# MICHA.net
KiCad netlist of a schematic drawn in EAGLE
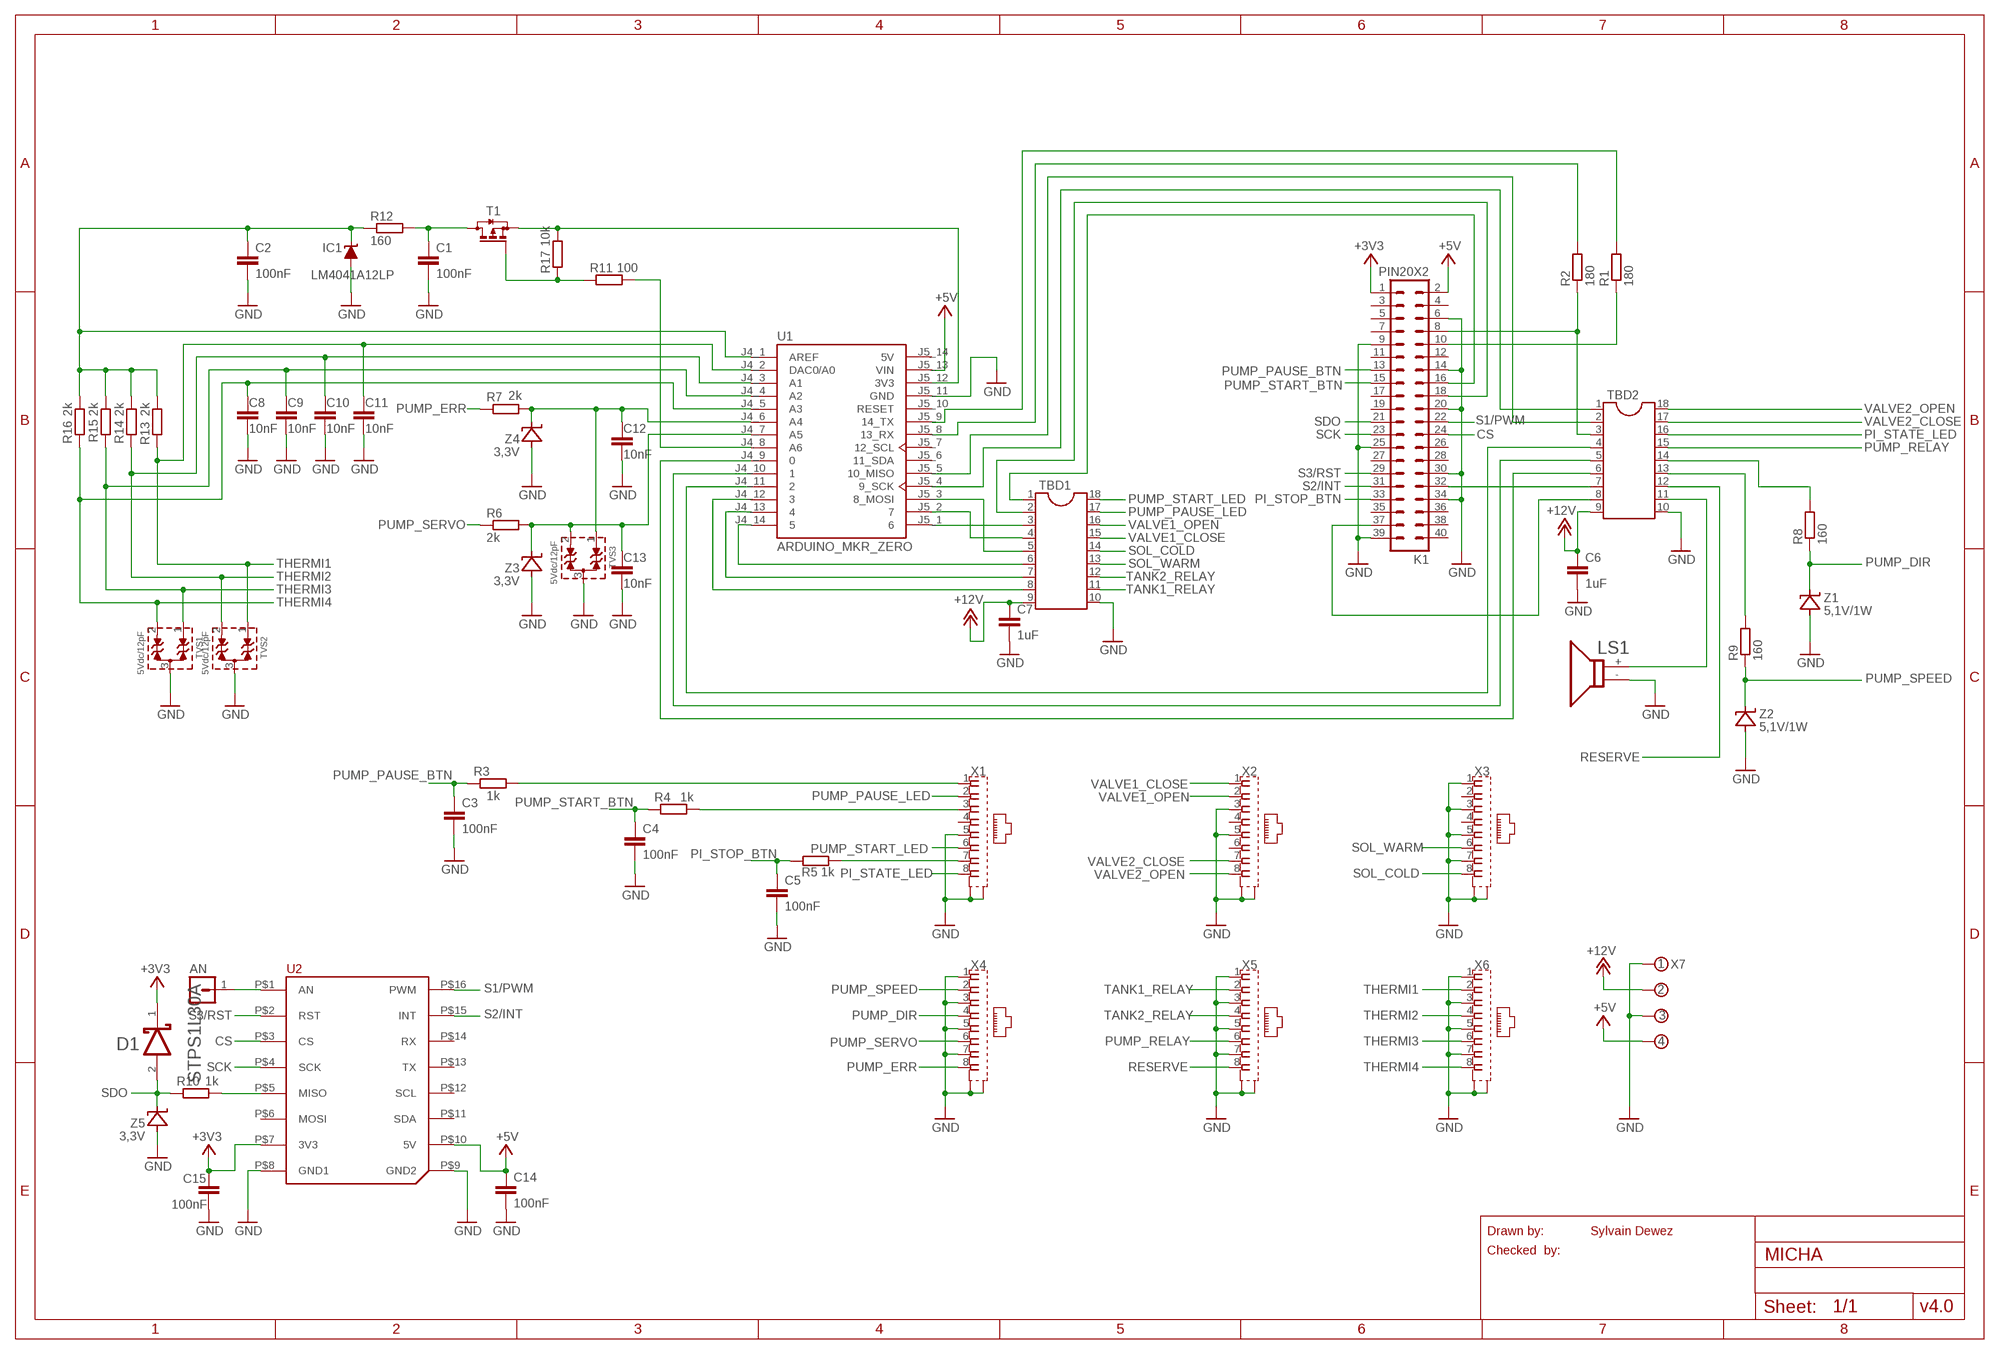
[diagram p0: schematic, sheet 1]

(export (version "E")
  (design (tool "Eeschema 10.0.6"))
  (components
    (comp (ref "AN")
      (value "MA01_PINHEADER")
      (footprint "eagle-import:MA01")
      (libsource (lib "eagle-import") (part "MA01_PINHEADER"))
    )
    (comp (ref "C1")
      (value "100nF")
      (footprint "eagle-import:C1206")
      (libsource (lib "eagle-import") (part "C-EUC1206"))
    )
    (comp (ref "C2")
      (value "100nF")
      (footprint "eagle-import:C1206")
      (libsource (lib "eagle-import") (part "C-EUC1206"))
    )
    (comp (ref "C3")
      (value "100nF")
      (footprint "eagle-import:C1206")
      (libsource (lib "eagle-import") (part "C-EUC1206"))
    )
    (comp (ref "C4")
      (value "100nF")
      (footprint "eagle-import:C1206")
      (libsource (lib "eagle-import") (part "C-EUC1206"))
    )
    (comp (ref "C5")
      (value "100nF")
      (footprint "eagle-import:C1206")
      (libsource (lib "eagle-import") (part "C-EUC1206"))
    )
    (comp (ref "C6")
      (value "1uF")
      (footprint "eagle-import:C1206")
      (libsource (lib "eagle-import") (part "C-EUC1206"))
    )
    (comp (ref "C7")
      (value "1uF")
      (footprint "eagle-import:C1206")
      (libsource (lib "eagle-import") (part "C-EUC1206"))
    )
    (comp (ref "C8")
      (value "10nF")
      (footprint "eagle-import:C1206")
      (libsource (lib "eagle-import") (part "C-EUC1206"))
    )
    (comp (ref "C9")
      (value "10nF")
      (footprint "eagle-import:C1206")
      (libsource (lib "eagle-import") (part "C-EUC1206"))
    )
    (comp (ref "C10")
      (value "10nF")
      (footprint "eagle-import:C1206")
      (libsource (lib "eagle-import") (part "C-EUC1206"))
    )
    (comp (ref "C11")
      (value "10nF")
      (footprint "eagle-import:C1206")
      (libsource (lib "eagle-import") (part "C-EUC1206"))
    )
    (comp (ref "C12")
      (value "10nF")
      (footprint "eagle-import:C1206")
      (libsource (lib "eagle-import") (part "C-EUC1206"))
    )
    (comp (ref "C13")
      (value "10nF")
      (footprint "eagle-import:C1206")
      (libsource (lib "eagle-import") (part "C-EUC1206"))
    )
    (comp (ref "C14")
      (value "100nF")
      (footprint "eagle-import:C1206")
      (libsource (lib "eagle-import") (part "C-EUC1206"))
    )
    (comp (ref "C15")
      (value "100nF")
      (footprint "eagle-import:C1206")
      (libsource (lib "eagle-import") (part "C-EUC1206"))
    )
    (comp (ref "D1")
      (value "STMICROELECTRONICS_STPS1L30ASTMICROELECTRONICS_STPS1L30A_0_0")
      (footprint "eagle-import:STMICROELECTRONICS_STPS1L30A_0")
      (fields
        (field (name "DIGIKEY_PART_NUMBER") "497-6577-1-ND")
        (field (name "MF") "STMicroelectronics")
        (field (name "MOUSER_PART_NUMBER") "511-STPS1L30A")
      )
      (libsource (lib "eagle-import") (part "STMICROELECTRONICS_STPS1L30ASTMICROELECTRONICS_STPS1L30A_0_0"))
    )
    (comp (ref "IC1")
      (value "LM4041A12LP")
      (footprint "eagle-import:LP_O-PBCY-W3")
      (libsource (lib "eagle-import") (part "LM4041LPA12"))
    )
    (comp (ref "K1")
      (value "PIN20X2")
      (footprint "eagle-import:PIN_20X2")
      (libsource (lib "eagle-import") (part "PIN20X2"))
    )
    (comp (ref "LS1")
      (value "RSPRO-BUZZER-7800743")
      (footprint "eagle-import:RSPRO-BUZZER-7800743")
      (libsource (lib "eagle-import") (part "RSPRO-BUZZER-7800743"))
    )
    (comp (ref "R1")
      (value "180")
      (footprint "eagle-import:R1206")
      (libsource (lib "eagle-import") (part "resistor_R-EU_R1206"))
    )
    (comp (ref "R2")
      (value "180")
      (footprint "eagle-import:R1206")
      (libsource (lib "eagle-import") (part "resistor_R-EU_R1206"))
    )
    (comp (ref "R3")
      (value "1k")
      (footprint "eagle-import:R1206")
      (libsource (lib "eagle-import") (part "resistor_R-EU_R1206"))
    )
    (comp (ref "R4")
      (value "1k")
      (footprint "eagle-import:R1206")
      (libsource (lib "eagle-import") (part "resistor_R-EU_R1206"))
    )
    (comp (ref "R5")
      (value "1k")
      (footprint "eagle-import:R1206")
      (libsource (lib "eagle-import") (part "resistor_R-EU_R1206"))
    )
    (comp (ref "R6")
      (value "2k")
      (footprint "eagle-import:R1206")
      (libsource (lib "eagle-import") (part "resistor_R-EU_R1206"))
    )
    (comp (ref "R7")
      (value "2k")
      (footprint "eagle-import:R1206")
      (libsource (lib "eagle-import") (part "resistor_R-EU_R1206"))
    )
    (comp (ref "R8")
      (value "160")
      (footprint "eagle-import:R1210")
      (libsource (lib "eagle-import") (part "R-EU_R1210"))
    )
    (comp (ref "R9")
      (value "160")
      (footprint "eagle-import:R1210")
      (libsource (lib "eagle-import") (part "R-EU_R1210"))
    )
    (comp (ref "R10")
      (value "1k")
      (footprint "eagle-import:R1206")
      (libsource (lib "eagle-import") (part "resistor_R-EU_R1206"))
    )
    (comp (ref "R11")
      (value "100")
      (footprint "eagle-import:R1206")
      (libsource (lib "eagle-import") (part "resistor_R-EU_R1206"))
    )
    (comp (ref "R12")
      (value "160")
      (footprint "eagle-import:R1210")
      (libsource (lib "eagle-import") (part "R-EU_R1210"))
    )
    (comp (ref "R13")
      (value "2k")
      (footprint "eagle-import:R1206")
      (libsource (lib "eagle-import") (part "resistor_R-EU_R1206"))
    )
    (comp (ref "R14")
      (value "2k")
      (footprint "eagle-import:R1206")
      (libsource (lib "eagle-import") (part "resistor_R-EU_R1206"))
    )
    (comp (ref "R15")
      (value "2k")
      (footprint "eagle-import:R1206")
      (libsource (lib "eagle-import") (part "resistor_R-EU_R1206"))
    )
    (comp (ref "R16")
      (value "2k")
      (footprint "eagle-import:R1206")
      (libsource (lib "eagle-import") (part "resistor_R-EU_R1206"))
    )
    (comp (ref "R17")
      (value "10k")
      (footprint "eagle-import:R1206")
      (libsource (lib "eagle-import") (part "resistor_R-EU_R1206"))
    )
    (comp (ref "T1")
      (value "BSS84")
      (footprint "eagle-import:SOT23")
      (libsource (lib "eagle-import") (part "BSS84"))
    )
    (comp (ref "TBD1")
      (value "DIL18S")
      (footprint "eagle-import:SOCKET-18")
      (libsource (lib "eagle-import") (part "DIL18S"))
    )
    (comp (ref "TBD2")
      (value "DIL18S")
      (footprint "eagle-import:SOCKET-18")
      (libsource (lib "eagle-import") (part "DIL18S"))
    )
    (comp (ref "TVS1")
      (value "5Vdc/12pF")
      (footprint "eagle-import:WE-TVS_SOT23-3L")
      (libsource (lib "eagle-import") (part "WE-TVS_SOT23-3L_824022"))
    )
    (comp (ref "TVS2")
      (value "5Vdc/12pF")
      (footprint "eagle-import:WE-TVS_SOT23-3L")
      (libsource (lib "eagle-import") (part "WE-TVS_SOT23-3L_824022"))
    )
    (comp (ref "TVS3")
      (value "5Vdc/12pF")
      (footprint "eagle-import:WE-TVS_SOT23-3L")
      (libsource (lib "eagle-import") (part "WE-TVS_SOT23-3L_824022"))
    )
    (comp (ref "U1")
      (value "ARDUINO_MKR_ZERO")
      (footprint "eagle-import:MODULE_ARDUINO_MKR_ZERO")
      (fields (field (name "MF") "Arduino") (field (name "MP") "ARDUINO MKR ZERO"))
      (libsource (lib "eagle-import") (part "ARDUINO_MKR_ZERO"))
    )
    (comp (ref "U2")
      (value "MIKROE_CLICK")
      (footprint "eagle-import:MIKROE_BUS_MIDI_NOLABEL")
      (libsource (lib "eagle-import") (part "MIKROE_CLICK"))
    )
    (comp (ref "X1")
      (value "RJ45-RJULE4318101")
      (footprint "eagle-import:RJ45-RJULE4318101")
      (libsource (lib "eagle-import") (part "RJ45-RJULE4318101"))
    )
    (comp (ref "X2")
      (value "RJ45-RJULE4318101")
      (footprint "eagle-import:RJ45-RJULE4318101")
      (libsource (lib "eagle-import") (part "RJ45-RJULE4318101"))
    )
    (comp (ref "X3")
      (value "RJ45-RJULE4318101")
      (footprint "eagle-import:RJ45-RJULE4318101")
      (libsource (lib "eagle-import") (part "RJ45-RJULE4318101"))
    )
    (comp (ref "X4")
      (value "RJ45-RJULE4318101")
      (footprint "eagle-import:RJ45-RJULE4318101")
      (libsource (lib "eagle-import") (part "RJ45-RJULE4318101"))
    )
    (comp (ref "X5")
      (value "RJ45-RJULE4318101")
      (footprint "eagle-import:RJ45-RJULE4318101")
      (libsource (lib "eagle-import") (part "RJ45-RJULE4318101"))
    )
    (comp (ref "X6")
      (value "RJ45-RJULE4318101")
      (footprint "eagle-import:RJ45-RJULE4318101")
      (libsource (lib "eagle-import") (part "RJ45-RJULE4318101"))
    )
    (comp (ref "X7")
      (value "BUCHANAN_4_3.5MM")
      (footprint "eagle-import:BUCHANAN_4_3.5MM")
      (libsource (lib "eagle-import") (part "BUCHANAN_4_3.5MM"))
    )
    (comp (ref "Z1")
      (value "5,1V/1W")
      (footprint "eagle-import:ZENER_SMA")
      (libsource (lib "eagle-import") (part "ZENER_SMA"))
    )
    (comp (ref "Z2")
      (value "5,1V/1W")
      (footprint "eagle-import:ZENER_SMA")
      (libsource (lib "eagle-import") (part "ZENER_SMA"))
    )
    (comp (ref "Z3")
      (value "3,3V")
      (footprint "eagle-import:ZENER_SMA")
      (libsource (lib "eagle-import") (part "ZENER_SMA"))
    )
    (comp (ref "Z4")
      (value "3,3V")
      (footprint "eagle-import:ZENER_SMA")
      (libsource (lib "eagle-import") (part "ZENER_SMA"))
    )
    (comp (ref "Z5")
      (value "3,3V")
      (footprint "eagle-import:ZENER_SMA")
      (libsource (lib "eagle-import") (part "ZENER_SMA"))
    )
  )
  (nets
    (net (code "1") (name "+3V3") (class "Default")
      (node (ref "C15") (pin "1") (pinfunction "1_1") (pintype "passive"))
      (node (ref "D1") (pin "1") (pinfunction "CATHODE_1") (pintype "bidirectional"))
      (node (ref "K1") (pin "1") (pinfunction "1_1") (pintype "passive"))
      (node (ref "U2") (pin "P$7") (pinfunction "3V3_P$7") (pintype "bidirectional"))
    )
    (net (code "2") (name "+5V") (class "Default")
      (node (ref "C14") (pin "1") (pinfunction "1_1") (pintype "passive"))
      (node (ref "K1") (pin "2") (pinfunction "2_2") (pintype "passive"))
      (node (ref "U1") (pin "J5_13") (pinfunction "VIN_J5_13") (pintype "power_in"))
      (node (ref "U2") (pin "P$10") (pinfunction "5V_P$10") (pintype "bidirectional"))
      (node (ref "X7") (pin "4") (pinfunction "KL3_4") (pintype "passive"))
    )
    (net (code "3") (name "+12V") (class "Default")
      (node (ref "C6") (pin "1") (pinfunction "1_1") (pintype "passive"))
      (node (ref "C7") (pin "1") (pinfunction "1_1") (pintype "passive"))
      (node (ref "TBD1") (pin "9") (pinfunction "9_9") (pintype "passive"))
      (node (ref "TBD2") (pin "9") (pinfunction "9_9") (pintype "passive"))
      (node (ref "X7") (pin "2") (pinfunction "KL1_2") (pintype "passive"))
    )
    (net (code "4") (name "/5V") (class "Default")
      (node (ref "U1") (pin "J5_14") (pinfunction "5V_J5_14") (pintype "power_in"))
    )
    (net (code "5") (name "/CS") (class "Default")
      (node (ref "K1") (pin "24") (pinfunction "24_24") (pintype "passive"))
      (node (ref "U2") (pin "P$3") (pinfunction "CS_P$3") (pintype "bidirectional"))
    )
    (net (code "6") (name "/PI_STATE_LED") (class "Default")
      (node (ref "TBD2") (pin "16") (pinfunction "16_16") (pintype "passive"))
      (node (ref "X1") (pin "8") (pinfunction "8_8") (pintype "passive"))
    )
    (net (code "7") (name "/PI_STOP_BTN") (class "Default")
      (node (ref "C5") (pin "1") (pinfunction "1_1") (pintype "passive"))
      (node (ref "K1") (pin "33") (pinfunction "33_33") (pintype "passive"))
      (node (ref "R5") (pin "1") (pinfunction "1_1") (pintype "passive"))
    )
    (net (code "8") (name "/PUMP_DIR") (class "Default")
      (node (ref "R8") (pin "1") (pinfunction "1_1") (pintype "passive"))
      (node (ref "X4") (pin "4") (pinfunction "4_4") (pintype "passive"))
      (node (ref "Z1") (pin "C") (pinfunction "C_C") (pintype "passive"))
    )
    (net (code "9") (name "/PUMP_ERR") (class "Default")
      (node (ref "R7") (pin "1") (pinfunction "1_1") (pintype "passive"))
      (node (ref "X4") (pin "8") (pinfunction "8_8") (pintype "passive"))
    )
    (net (code "10") (name "/PUMP_PAUSE_BTN") (class "Default")
      (node (ref "C3") (pin "1") (pinfunction "1_1") (pintype "passive"))
      (node (ref "K1") (pin "13") (pinfunction "13_13") (pintype "passive"))
      (node (ref "R3") (pin "1") (pinfunction "1_1") (pintype "passive"))
    )
    (net (code "11") (name "/PUMP_PAUSE_LED") (class "Default")
      (node (ref "TBD1") (pin "17") (pinfunction "17_17") (pintype "passive"))
      (node (ref "X1") (pin "2") (pinfunction "2_2") (pintype "passive"))
    )
    (net (code "12") (name "/PUMP_RELAY") (class "Default")
      (node (ref "TBD2") (pin "15") (pinfunction "15_15") (pintype "passive"))
      (node (ref "X5") (pin "6") (pinfunction "6_6") (pintype "passive"))
    )
    (net (code "13") (name "/PUMP_SERVO") (class "Default")
      (node (ref "R6") (pin "1") (pinfunction "1_1") (pintype "passive"))
      (node (ref "X4") (pin "6") (pinfunction "6_6") (pintype "passive"))
    )
    (net (code "14") (name "/PUMP_SPEED") (class "Default")
      (node (ref "R9") (pin "1") (pinfunction "1_1") (pintype "passive"))
      (node (ref "X4") (pin "2") (pinfunction "2_2") (pintype "passive"))
      (node (ref "Z2") (pin "C") (pinfunction "C_C") (pintype "passive"))
    )
    (net (code "15") (name "/PUMP_START_BTN") (class "Default")
      (node (ref "C4") (pin "1") (pinfunction "1_1") (pintype "passive"))
      (node (ref "K1") (pin "15") (pinfunction "15_15") (pintype "passive"))
      (node (ref "R4") (pin "1") (pinfunction "1_1") (pintype "passive"))
    )
    (net (code "16") (name "/PUMP_START_LED") (class "Default")
      (node (ref "TBD1") (pin "18") (pinfunction "18_18") (pintype "passive"))
      (node (ref "X1") (pin "6") (pinfunction "6_6") (pintype "passive"))
    )
    (net (code "17") (name "/RESERVE") (class "Default")
      (node (ref "TBD2") (pin "12") (pinfunction "12_12") (pintype "passive"))
      (node (ref "X5") (pin "8") (pinfunction "8_8") (pintype "passive"))
    )
    (net (code "18") (name "/S1{slash}PWM") (class "Default")
      (node (ref "K1") (pin "22") (pinfunction "22_22") (pintype "passive"))
      (node (ref "U2") (pin "P$16") (pinfunction "PWM_P$16") (pintype "bidirectional"))
    )
    (net (code "19") (name "/S2{slash}INT") (class "Default")
      (node (ref "K1") (pin "31") (pinfunction "31_31") (pintype "passive"))
      (node (ref "U2") (pin "P$15") (pinfunction "INT_P$15") (pintype "bidirectional"))
    )
    (net (code "20") (name "/S3{slash}RST") (class "Default")
      (node (ref "K1") (pin "29") (pinfunction "29_29") (pintype "passive"))
      (node (ref "U2") (pin "P$2") (pinfunction "RST_P$2") (pintype "bidirectional"))
    )
    (net (code "21") (name "/SCK") (class "Default")
      (node (ref "K1") (pin "23") (pinfunction "23_23") (pintype "passive"))
      (node (ref "U2") (pin "P$4") (pinfunction "SCK_P$4") (pintype "bidirectional"))
    )
    (net (code "22") (name "/SDO") (class "Default")
      (node (ref "D1") (pin "2") (pinfunction "ANODE_2") (pintype "bidirectional"))
      (node (ref "K1") (pin "21") (pinfunction "21_21") (pintype "passive"))
      (node (ref "R10") (pin "1") (pinfunction "1_1") (pintype "passive"))
      (node (ref "Z5") (pin "C") (pinfunction "C_C") (pintype "passive"))
    )
    (net (code "23") (name "/SOL_COLD") (class "Default")
      (node (ref "TBD1") (pin "14") (pinfunction "14_14") (pintype "passive"))
      (node (ref "X3") (pin "8") (pinfunction "8_8") (pintype "passive"))
    )
    (net (code "24") (name "/SOL_WARM") (class "Default")
      (node (ref "TBD1") (pin "13") (pinfunction "13_13") (pintype "passive"))
      (node (ref "X3") (pin "6") (pinfunction "6_6") (pintype "passive"))
    )
    (net (code "25") (name "/TANK1_RELAY") (class "Default")
      (node (ref "TBD1") (pin "11") (pinfunction "11_11") (pintype "passive"))
      (node (ref "X5") (pin "2") (pinfunction "2_2") (pintype "passive"))
    )
    (net (code "26") (name "/TANK2_RELAY") (class "Default")
      (node (ref "TBD1") (pin "12") (pinfunction "12_12") (pintype "passive"))
      (node (ref "X5") (pin "4") (pinfunction "4_4") (pintype "passive"))
    )
    (net (code "27") (name "/THERMI1") (class "Default")
      (node (ref "C11") (pin "1") (pinfunction "1_1") (pintype "passive"))
      (node (ref "R13") (pin "2") (pinfunction "2_2") (pintype "passive"))
      (node (ref "TVS2") (pin "1") (pinfunction "I/O1_1") (pintype "bidirectional"))
      (node (ref "U1") (pin "J4_2") (pinfunction "DAC0/A0_J4_2") (pintype "bidirectional"))
      (node (ref "X6") (pin "2") (pinfunction "2_2") (pintype "passive"))
    )
    (net (code "28") (name "/THERMI2") (class "Default")
      (node (ref "C10") (pin "1") (pinfunction "1_1") (pintype "passive"))
      (node (ref "R14") (pin "2") (pinfunction "2_2") (pintype "passive"))
      (node (ref "TVS2") (pin "2") (pinfunction "I/O2_2") (pintype "bidirectional"))
      (node (ref "U1") (pin "J4_3") (pinfunction "A1_J4_3") (pintype "bidirectional"))
      (node (ref "X6") (pin "4") (pinfunction "4_4") (pintype "passive"))
    )
    (net (code "29") (name "/THERMI3") (class "Default")
      (node (ref "C9") (pin "1") (pinfunction "1_1") (pintype "passive"))
      (node (ref "R15") (pin "2") (pinfunction "2_2") (pintype "passive"))
      (node (ref "TVS1") (pin "1") (pinfunction "I/O1_1") (pintype "bidirectional"))
      (node (ref "U1") (pin "J4_4") (pinfunction "A2_J4_4") (pintype "bidirectional"))
      (node (ref "X6") (pin "6") (pinfunction "6_6") (pintype "passive"))
    )
    (net (code "30") (name "/THERMI4") (class "Default")
      (node (ref "C8") (pin "1") (pinfunction "1_1") (pintype "passive"))
      (node (ref "R16") (pin "2") (pinfunction "2_2") (pintype "passive"))
      (node (ref "TVS1") (pin "2") (pinfunction "I/O2_2") (pintype "bidirectional"))
      (node (ref "U1") (pin "J4_5") (pinfunction "A3_J4_5") (pintype "bidirectional"))
      (node (ref "X6") (pin "8") (pinfunction "8_8") (pintype "passive"))
    )
    (net (code "31") (name "/VALVE1_CLOSE") (class "Default")
      (node (ref "TBD1") (pin "15") (pinfunction "15_15") (pintype "passive"))
      (node (ref "X2") (pin "1") (pinfunction "1_1") (pintype "passive"))
    )
    (net (code "32") (name "/VALVE1_OPEN") (class "Default")
      (node (ref "TBD1") (pin "16") (pinfunction "16_16") (pintype "passive"))
      (node (ref "X2") (pin "2") (pinfunction "2_2") (pintype "passive"))
    )
    (net (code "33") (name "/VALVE2_CLOSE") (class "Default")
      (node (ref "TBD2") (pin "17") (pinfunction "17_17") (pintype "passive"))
      (node (ref "X2") (pin "7") (pinfunction "7_7") (pintype "passive"))
    )
    (net (code "34") (name "/VALVE2_OPEN") (class "Default")
      (node (ref "TBD2") (pin "18") (pinfunction "18_18") (pintype "passive"))
      (node (ref "X2") (pin "8") (pinfunction "8_8") (pintype "passive"))
    )
    (net (code "35") (name "GND") (class "Default")
      (node (ref "C1") (pin "2") (pinfunction "2_2") (pintype "passive"))
      (node (ref "C10") (pin "2") (pinfunction "2_2") (pintype "passive"))
      (node (ref "C11") (pin "2") (pinfunction "2_2") (pintype "passive"))
      (node (ref "C12") (pin "2") (pinfunction "2_2") (pintype "passive"))
      (node (ref "C13") (pin "2") (pinfunction "2_2") (pintype "passive"))
      (node (ref "C14") (pin "2") (pinfunction "2_2") (pintype "passive"))
      (node (ref "C15") (pin "2") (pinfunction "2_2") (pintype "passive"))
      (node (ref "C2") (pin "2") (pinfunction "2_2") (pintype "passive"))
      (node (ref "C3") (pin "2") (pinfunction "2_2") (pintype "passive"))
      (node (ref "C4") (pin "2") (pinfunction "2_2") (pintype "passive"))
      (node (ref "C5") (pin "2") (pinfunction "2_2") (pintype "passive"))
      (node (ref "C6") (pin "2") (pinfunction "2_2") (pintype "passive"))
      (node (ref "C7") (pin "2") (pinfunction "2_2") (pintype "passive"))
      (node (ref "C8") (pin "2") (pinfunction "2_2") (pintype "passive"))
      (node (ref "C9") (pin "2") (pinfunction "2_2") (pintype "passive"))
      (node (ref "IC1") (pin "3") (pinfunction "A_3") (pintype "passive"))
      (node (ref "K1") (pin "14") (pinfunction "14_14") (pintype "passive"))
      (node (ref "K1") (pin "20") (pinfunction "20_20") (pintype "passive"))
      (node (ref "K1") (pin "25") (pinfunction "25_25") (pintype "passive"))
      (node (ref "K1") (pin "30") (pinfunction "30_30") (pintype "passive"))
      (node (ref "K1") (pin "34") (pinfunction "34_34") (pintype "passive"))
      (node (ref "K1") (pin "39") (pinfunction "39_39") (pintype "passive"))
      (node (ref "K1") (pin "6") (pinfunction "6_6") (pintype "passive"))
      (node (ref "K1") (pin "9") (pinfunction "9_9") (pintype "passive"))
      (node (ref "LS1") (pin "-") (pinfunction "2_-") (pintype "passive"))
      (node (ref "TBD1") (pin "10") (pinfunction "10_10") (pintype "passive"))
      (node (ref "TBD2") (pin "10") (pinfunction "10_10") (pintype "passive"))
      (node (ref "TVS1") (pin "3") (pinfunction "GND_3") (pintype "power_in"))
      (node (ref "TVS2") (pin "3") (pinfunction "GND_3") (pintype "power_in"))
      (node (ref "TVS3") (pin "3") (pinfunction "GND_3") (pintype "power_in"))
      (node (ref "U1") (pin "J5_11") (pinfunction "GND_J5_11") (pintype "power_in"))
      (node (ref "U2") (pin "P$8") (pinfunction "GND1_P$8") (pintype "bidirectional"))
      (node (ref "U2") (pin "P$9") (pinfunction "GND2_P$9") (pintype "bidirectional"))
      (node (ref "X1") (pin "5") (pinfunction "5_5") (pintype "passive"))
      (node (ref "X1") (pin "GND1") (pinfunction "GND1_GND1") (pintype "passive"))
      (node (ref "X1") (pin "GND2") (pinfunction "GND2_GND2") (pintype "passive"))
      (node (ref "X2") (pin "3") (pinfunction "3_3") (pintype "passive"))
      (node (ref "X2") (pin "5") (pinfunction "5_5") (pintype "passive"))
      (node (ref "X2") (pin "GND1") (pinfunction "GND1_GND1") (pintype "passive"))
      (node (ref "X2") (pin "GND2") (pinfunction "GND2_GND2") (pintype "passive"))
      (node (ref "X3") (pin "1") (pinfunction "1_1") (pintype "passive"))
      (node (ref "X3") (pin "3") (pinfunction "3_3") (pintype "passive"))
      (node (ref "X3") (pin "5") (pinfunction "5_5") (pintype "passive"))
      (node (ref "X3") (pin "7") (pinfunction "7_7") (pintype "passive"))
      (node (ref "X3") (pin "GND1") (pinfunction "GND1_GND1") (pintype "passive"))
      (node (ref "X3") (pin "GND2") (pinfunction "GND2_GND2") (pintype "passive"))
      (node (ref "X4") (pin "1") (pinfunction "1_1") (pintype "passive"))
      (node (ref "X4") (pin "3") (pinfunction "3_3") (pintype "passive"))
      (node (ref "X4") (pin "5") (pinfunction "5_5") (pintype "passive"))
      (node (ref "X4") (pin "7") (pinfunction "7_7") (pintype "passive"))
      (node (ref "X4") (pin "GND1") (pinfunction "GND1_GND1") (pintype "passive"))
      (node (ref "X4") (pin "GND2") (pinfunction "GND2_GND2") (pintype "passive"))
      (node (ref "X5") (pin "1") (pinfunction "1_1") (pintype "passive"))
      (node (ref "X5") (pin "3") (pinfunction "3_3") (pintype "passive"))
      (node (ref "X5") (pin "5") (pinfunction "5_5") (pintype "passive"))
      (node (ref "X5") (pin "7") (pinfunction "7_7") (pintype "passive"))
      (node (ref "X5") (pin "GND1") (pinfunction "GND1_GND1") (pintype "passive"))
      (node (ref "X5") (pin "GND2") (pinfunction "GND2_GND2") (pintype "passive"))
      (node (ref "X6") (pin "1") (pinfunction "1_1") (pintype "passive"))
      (node (ref "X6") (pin "3") (pinfunction "3_3") (pintype "passive"))
      (node (ref "X6") (pin "5") (pinfunction "5_5") (pintype "passive"))
      (node (ref "X6") (pin "7") (pinfunction "7_7") (pintype "passive"))
      (node (ref "X6") (pin "GND1") (pinfunction "GND1_GND1") (pintype "passive"))
      (node (ref "X6") (pin "GND2") (pinfunction "GND2_GND2") (pintype "passive"))
      (node (ref "X7") (pin "1") (pinfunction "KL_1") (pintype "passive"))
      (node (ref "X7") (pin "3") (pinfunction "KL2_3") (pintype "passive"))
      (node (ref "Z1") (pin "A") (pinfunction "A_A") (pintype "passive"))
      (node (ref "Z2") (pin "A") (pinfunction "A_A") (pintype "passive"))
      (node (ref "Z3") (pin "A") (pinfunction "A_A") (pintype "passive"))
      (node (ref "Z4") (pin "A") (pinfunction "A_A") (pintype "passive"))
      (node (ref "Z5") (pin "A") (pinfunction "A_A") (pintype "passive"))
    )
    (net (code "36") (name "Net-(IC1-C)") (class "Default")
      (node (ref "C2") (pin "1") (pinfunction "1_1") (pintype "passive"))
      (node (ref "IC1") (pin "2") (pinfunction "C_2") (pintype "passive"))
      (node (ref "R12") (pin "1") (pinfunction "1_1") (pintype "passive"))
      (node (ref "R13") (pin "1") (pinfunction "1_1") (pintype "passive"))
      (node (ref "R14") (pin "1") (pinfunction "1_1") (pintype "passive"))
      (node (ref "R15") (pin "1") (pinfunction "1_1") (pintype "passive"))
      (node (ref "R16") (pin "1") (pinfunction "1_1") (pintype "passive"))
      (node (ref "U1") (pin "J4_1") (pinfunction "AREF_J4_1") (pintype "bidirectional"))
    )
    (net (code "37") (name "Net-(K1-Pad8)") (class "Default")
      (node (ref "K1") (pin "8") (pinfunction "8_8") (pintype "passive"))
      (node (ref "R2") (pin "1") (pinfunction "1_1") (pintype "passive"))
      (node (ref "TBD2") (pin "3") (pinfunction "3_3") (pintype "passive"))
    )
    (net (code "38") (name "Net-(K1-Pad10)") (class "Default")
      (node (ref "K1") (pin "10") (pinfunction "10_10") (pintype "passive"))
      (node (ref "R1") (pin "1") (pinfunction "1_1") (pintype "passive"))
    )
    (net (code "39") (name "Net-(K1-Pad16)") (class "Default")
      (node (ref "K1") (pin "16") (pinfunction "16_16") (pintype "passive"))
      (node (ref "TBD1") (pin "1") (pinfunction "1_1") (pintype "passive"))
    )
    (net (code "40") (name "Net-(K1-Pad18)") (class "Default")
      (node (ref "K1") (pin "18") (pinfunction "18_18") (pintype "passive"))
      (node (ref "TBD1") (pin "2") (pinfunction "2_2") (pintype "passive"))
    )
    (net (code "41") (name "Net-(K1-Pad32)") (class "Default")
      (node (ref "K1") (pin "32") (pinfunction "32_32") (pintype "passive"))
      (node (ref "TBD2") (pin "7") (pinfunction "7_7") (pintype "passive"))
    )
    (net (code "42") (name "Net-(K1-Pad37)") (class "Default")
      (node (ref "K1") (pin "37") (pinfunction "37_37") (pintype "passive"))
      (node (ref "TBD2") (pin "8") (pinfunction "8_8") (pintype "passive"))
    )
    (net (code "43") (name "Net-(LS1-1)") (class "Default")
      (node (ref "LS1") (pin "+") (pinfunction "1_+") (pintype "passive"))
      (node (ref "TBD2") (pin "11") (pinfunction "11_11") (pintype "passive"))
    )
    (net (code "44") (name "Net-(R3-Pad2)") (class "Default")
      (node (ref "R3") (pin "2") (pinfunction "2_2") (pintype "passive"))
      (node (ref "X1") (pin "1") (pinfunction "1_1") (pintype "passive"))
    )
    (net (code "45") (name "Net-(R4-Pad2)") (class "Default")
      (node (ref "R4") (pin "2") (pinfunction "2_2") (pintype "passive"))
      (node (ref "X1") (pin "3") (pinfunction "3_3") (pintype "passive"))
    )
    (net (code "46") (name "Net-(R5-Pad2)") (class "Default")
      (node (ref "R5") (pin "2") (pinfunction "2_2") (pintype "passive"))
      (node (ref "X1") (pin "7") (pinfunction "7_7") (pintype "passive"))
    )
    (net (code "47") (name "Net-(R8-Pad2)") (class "Default")
      (node (ref "R8") (pin "2") (pinfunction "2_2") (pintype "passive"))
      (node (ref "TBD2") (pin "14") (pinfunction "14_14") (pintype "passive"))
    )
    (net (code "48") (name "Net-(R9-Pad2)") (class "Default")
      (node (ref "R9") (pin "2") (pinfunction "2_2") (pintype "passive"))
      (node (ref "TBD2") (pin "13") (pinfunction "13_13") (pintype "passive"))
    )
    (net (code "49") (name "Net-(T1-D)") (class "Default")
      (node (ref "C1") (pin "1") (pinfunction "1_1") (pintype "passive"))
      (node (ref "R12") (pin "2") (pinfunction "2_2") (pintype "passive"))
      (node (ref "T1") (pin "3") (pinfunction "D_3") (pintype "passive"))
    )
    (net (code "50") (name "Net-(T1-G)") (class "Default")
      (node (ref "R11") (pin "1") (pinfunction "1_1") (pintype "passive"))
      (node (ref "R17") (pin "1") (pinfunction "1_1") (pintype "passive"))
      (node (ref "T1") (pin "1") (pinfunction "G_1") (pintype "passive"))
    )
    (net (code "51") (name "Net-(T1-S)") (class "Default")
      (node (ref "R17") (pin "2") (pinfunction "2_2") (pintype "passive"))
      (node (ref "T1") (pin "2") (pinfunction "S_2") (pintype "passive"))
      (node (ref "U1") (pin "J5_12") (pinfunction "3V3_J5_12") (pintype "power_in"))
    )
    (net (code "52") (name "Net-(TVS3-I{slash}O1)") (class "Default")
      (node (ref "C12") (pin "1") (pinfunction "1_1") (pintype "passive"))
      (node (ref "R7") (pin "2") (pinfunction "2_2") (pintype "passive"))
      (node (ref "TVS3") (pin "1") (pinfunction "I/O1_1") (pintype "bidirectional"))
      (node (ref "U1") (pin "J4_6") (pinfunction "A4_J4_6") (pintype "bidirectional"))
      (node (ref "Z4") (pin "C") (pinfunction "C_C") (pintype "passive"))
    )
    (net (code "53") (name "Net-(TVS3-I{slash}O2)") (class "Default")
      (node (ref "C13") (pin "1") (pinfunction "1_1") (pintype "passive"))
      (node (ref "R6") (pin "2") (pinfunction "2_2") (pintype "passive"))
      (node (ref "TVS3") (pin "2") (pinfunction "I/O2_2") (pintype "bidirectional"))
      (node (ref "U1") (pin "J4_7") (pinfunction "A5_J4_7") (pintype "bidirectional"))
      (node (ref "Z3") (pin "C") (pinfunction "C_C") (pintype "passive"))
    )
    (net (code "54") (name "Net-(U1-0)") (class "Default")
      (node (ref "TBD2") (pin "6") (pinfunction "6_6") (pintype "passive"))
      (node (ref "U1") (pin "J4_9") (pinfunction "0_J4_9") (pintype "bidirectional"))
    )
    (net (code "55") (name "Net-(U1-1)") (class "Default")
      (node (ref "TBD2") (pin "5") (pinfunction "5_5") (pintype "passive"))
      (node (ref "U1") (pin "J4_10") (pinfunction "1_J4_10") (pintype "bidirectional"))
    )
    (net (code "56") (name "Net-(U1-2)") (class "Default")
      (node (ref "TBD2") (pin "4") (pinfunction "4_4") (pintype "passive"))
      (node (ref "U1") (pin "J4_11") (pinfunction "2_J4_11") (pintype "bidirectional"))
    )
    (net (code "57") (name "Net-(U1-3)") (class "Default")
      (node (ref "TBD1") (pin "8") (pinfunction "8_8") (pintype "passive"))
      (node (ref "U1") (pin "J4_12") (pinfunction "3_J4_12") (pintype "bidirectional"))
    )
    (net (code "58") (name "Net-(U1-4)") (class "Default")
      (node (ref "TBD1") (pin "7") (pinfunction "7_7") (pintype "passive"))
      (node (ref "U1") (pin "J4_13") (pinfunction "4_J4_13") (pintype "bidirectional"))
    )
    (net (code "59") (name "Net-(U1-5)") (class "Default")
      (node (ref "TBD1") (pin "6") (pinfunction "6_6") (pintype "passive"))
      (node (ref "U1") (pin "J4_14") (pinfunction "5_J4_14") (pintype "bidirectional"))
    )
    (net (code "60") (name "Net-(U1-6)") (class "Default")
      (node (ref "TBD1") (pin "3") (pinfunction "3_3") (pintype "passive"))
      (node (ref "U1") (pin "J5_1") (pinfunction "6_J5_1") (pintype "bidirectional"))
    )
    (net (code "61") (name "Net-(U1-7)") (class "Default")
      (node (ref "TBD1") (pin "4") (pinfunction "4_4") (pintype "passive"))
      (node (ref "U1") (pin "J5_2") (pinfunction "7_J5_2") (pintype "bidirectional"))
    )
    (net (code "62") (name "Net-(U1-8_MOSI)") (class "Default")
      (node (ref "TBD1") (pin "5") (pinfunction "5_5") (pintype "passive"))
      (node (ref "U1") (pin "J5_3") (pinfunction "8_MOSI_J5_3") (pintype "bidirectional"))
    )
    (net (code "63") (name "Net-(U1-9_SCK)") (class "Default")
      (node (ref "TBD2") (pin "1") (pinfunction "1_1") (pintype "passive"))
      (node (ref "U1") (pin "J5_4") (pinfunction "9_SCK_J5_4") (pintype "bidirectional"))
    )
    (net (code "64") (name "Net-(U1-10_MISO)") (class "Default")
      (node (ref "TBD2") (pin "2") (pinfunction "2_2") (pintype "passive"))
      (node (ref "U1") (pin "J5_5") (pinfunction "10_MISO_J5_5") (pintype "bidirectional"))
    )
    (net (code "65") (name "Net-(U1-13_RX)") (class "Default")
      (node (ref "R2") (pin "2") (pinfunction "2_2") (pintype "passive"))
      (node (ref "U1") (pin "J5_8") (pinfunction "13_RX_J5_8") (pintype "input"))
    )
    (net (code "66") (name "Net-(U1-14_TX)") (class "Default")
      (node (ref "R1") (pin "2") (pinfunction "2_2") (pintype "passive"))
      (node (ref "U1") (pin "J5_9") (pinfunction "14_TX_J5_9") (pintype "output"))
    )
    (net (code "67") (name "Net-(U1-A6)") (class "Default")
      (node (ref "R11") (pin "2") (pinfunction "2_2") (pintype "passive"))
      (node (ref "U1") (pin "J4_8") (pinfunction "A6_J4_8") (pintype "bidirectional"))
    )
    (net (code "68") (name "Net-(U2-AN)") (class "Default")
      (node (ref "AN") (pin "1") (pinfunction "1_1") (pintype "passive"))
      (node (ref "U2") (pin "P$1") (pinfunction "AN_P$1") (pintype "bidirectional"))
    )
    (net (code "69") (name "Net-(U2-MISO)") (class "Default")
      (node (ref "R10") (pin "2") (pinfunction "2_2") (pintype "passive"))
      (node (ref "U2") (pin "P$5") (pinfunction "MISO_P$5") (pintype "bidirectional"))
    )
    (net (code "70") (name "unconnected-(K1-Pad3)") (class "Default")
      (node (ref "K1") (pin "3") (pinfunction "3_3") (pintype "passive"))
    )
    (net (code "71") (name "unconnected-(K1-Pad4)") (class "Default")
      (node (ref "K1") (pin "4") (pinfunction "4_4") (pintype "passive"))
    )
    (net (code "72") (name "unconnected-(K1-Pad5)") (class "Default")
      (node (ref "K1") (pin "5") (pinfunction "5_5") (pintype "passive"))
    )
    (net (code "73") (name "unconnected-(K1-Pad7)") (class "Default")
      (node (ref "K1") (pin "7") (pinfunction "7_7") (pintype "passive"))
    )
    (net (code "74") (name "unconnected-(K1-Pad11)") (class "Default")
      (node (ref "K1") (pin "11") (pinfunction "11_11") (pintype "passive"))
    )
    (net (code "75") (name "unconnected-(K1-Pad12)") (class "Default")
      (node (ref "K1") (pin "12") (pinfunction "12_12") (pintype "passive"))
    )
    (net (code "76") (name "unconnected-(K1-Pad17)") (class "Default")
      (node (ref "K1") (pin "17") (pinfunction "17_17") (pintype "passive"))
    )
    (net (code "77") (name "unconnected-(K1-Pad19)") (class "Default")
      (node (ref "K1") (pin "19") (pinfunction "19_19") (pintype "passive"))
    )
    (net (code "78") (name "unconnected-(K1-Pad26)") (class "Default")
      (node (ref "K1") (pin "26") (pinfunction "26_26") (pintype "passive"))
    )
    (net (code "79") (name "unconnected-(K1-Pad27)") (class "Default")
      (node (ref "K1") (pin "27") (pinfunction "27_27") (pintype "passive"))
    )
    (net (code "80") (name "unconnected-(K1-Pad28)") (class "Default")
      (node (ref "K1") (pin "28") (pinfunction "28_28") (pintype "passive"))
    )
    (net (code "81") (name "unconnected-(K1-Pad35)") (class "Default")
      (node (ref "K1") (pin "35") (pinfunction "35_35") (pintype "passive"))
    )
    (net (code "82") (name "unconnected-(K1-Pad36)") (class "Default")
      (node (ref "K1") (pin "36") (pinfunction "36_36") (pintype "passive"))
    )
    (net (code "83") (name "unconnected-(K1-Pad38)") (class "Default")
      (node (ref "K1") (pin "38") (pinfunction "38_38") (pintype "passive"))
    )
    (net (code "84") (name "unconnected-(K1-Pad40)") (class "Default")
      (node (ref "K1") (pin "40") (pinfunction "40_40") (pintype "passive"))
    )
    (net (code "85") (name "unconnected-(U1-11_SDA-PadJ5_6)") (class "Default")
      (node (ref "U1") (pin "J5_6") (pinfunction "11_SDA_J5_6") (pintype "bidirectional"))
    )
    (net (code "86") (name "unconnected-(U1-12_SCL-PadJ5_7)") (class "Default")
      (node (ref "U1") (pin "J5_7") (pinfunction "12_SCL_J5_7") (pintype "bidirectional"))
    )
    (net (code "87") (name "unconnected-(U1-RESET-PadJ5_10)") (class "Default")
      (node (ref "U1") (pin "J5_10") (pinfunction "RESET_J5_10") (pintype "bidirectional"))
    )
    (net (code "88") (name "unconnected-(U2-MOSI-PadP$6)") (class "Default")
      (node (ref "U2") (pin "P$6") (pinfunction "MOSI_P$6") (pintype "bidirectional"))
    )
    (net (code "89") (name "unconnected-(U2-RX-PadP$14)") (class "Default")
      (node (ref "U2") (pin "P$14") (pinfunction "RX_P$14") (pintype "bidirectional"))
    )
    (net (code "90") (name "unconnected-(U2-SCL-PadP$12)") (class "Default")
      (node (ref "U2") (pin "P$12") (pinfunction "SCL_P$12") (pintype "bidirectional"))
    )
    (net (code "91") (name "unconnected-(U2-SDA-PadP$11)") (class "Default")
      (node (ref "U2") (pin "P$11") (pinfunction "SDA_P$11") (pintype "bidirectional"))
    )
    (net (code "92") (name "unconnected-(U2-TX-PadP$13)") (class "Default")
      (node (ref "U2") (pin "P$13") (pinfunction "TX_P$13") (pintype "bidirectional"))
    )
    (net (code "93") (name "unconnected-(X1-Pad4)") (class "Default")
      (node (ref "X1") (pin "4") (pinfunction "4_4") (pintype "passive"))
    )
    (net (code "94") (name "unconnected-(X2-Pad4)") (class "Default")
      (node (ref "X2") (pin "4") (pinfunction "4_4") (pintype "passive"))
    )
    (net (code "95") (name "unconnected-(X2-Pad6)") (class "Default")
      (node (ref "X2") (pin "6") (pinfunction "6_6") (pintype "passive"))
    )
    (net (code "96") (name "unconnected-(X3-Pad2)") (class "Default")
      (node (ref "X3") (pin "2") (pinfunction "2_2") (pintype "passive"))
    )
    (net (code "97") (name "unconnected-(X3-Pad4)") (class "Default")
      (node (ref "X3") (pin "4") (pinfunction "4_4") (pintype "passive"))
    )
  )
)
